# Weihnachtsstern.net
KiCad netlist of a schematic drawn in EAGLE
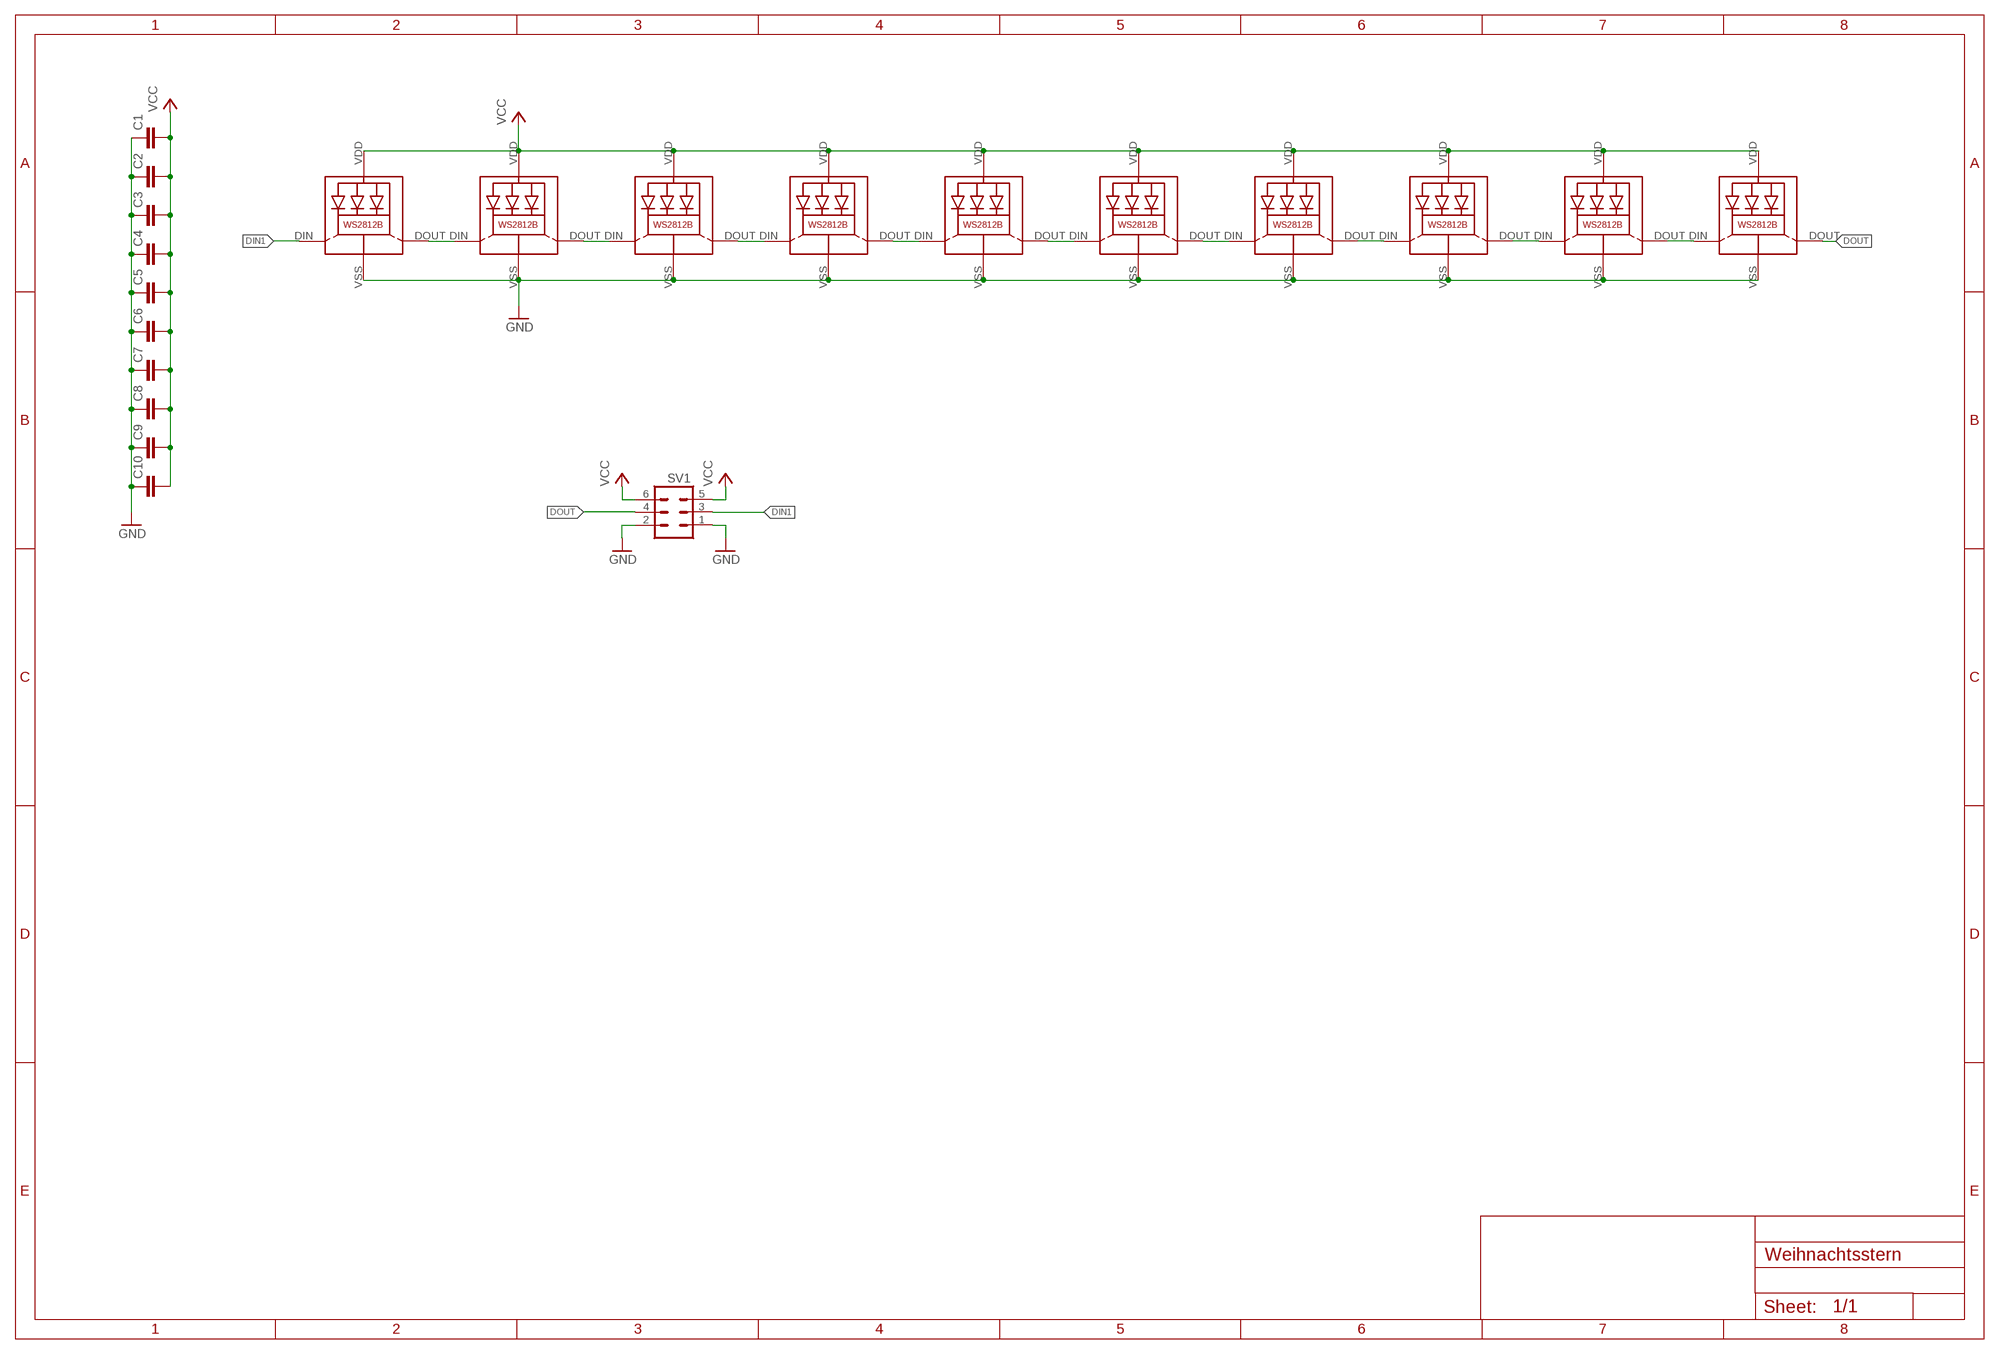
[diagram p0: schematic, sheet 1]

(export (version "E")
  (design (tool "Eeschema 10.0.6"))
  (components
    (comp (ref "C1")
      (value "C-EUC0805")
      (footprint "eagle-import:C0805")
      (libsource (lib "eagle-import") (part "C-EUC0805"))
    )
    (comp (ref "C2")
      (value "C-EUC0805")
      (footprint "eagle-import:C0805")
      (libsource (lib "eagle-import") (part "C-EUC0805"))
    )
    (comp (ref "C3")
      (value "C-EUC0805")
      (footprint "eagle-import:C0805")
      (libsource (lib "eagle-import") (part "C-EUC0805"))
    )
    (comp (ref "C4")
      (value "C-EUC0805")
      (footprint "eagle-import:C0805")
      (libsource (lib "eagle-import") (part "C-EUC0805"))
    )
    (comp (ref "C5")
      (value "C-EUC0805")
      (footprint "eagle-import:C0805")
      (libsource (lib "eagle-import") (part "C-EUC0805"))
    )
    (comp (ref "C6")
      (value "C-EUC0805")
      (footprint "eagle-import:C0805")
      (libsource (lib "eagle-import") (part "C-EUC0805"))
    )
    (comp (ref "C7")
      (value "C-EUC0805")
      (footprint "eagle-import:C0805")
      (libsource (lib "eagle-import") (part "C-EUC0805"))
    )
    (comp (ref "C8")
      (value "C-EUC0805")
      (footprint "eagle-import:C0805")
      (libsource (lib "eagle-import") (part "C-EUC0805"))
    )
    (comp (ref "C9")
      (value "C-EUC0805")
      (footprint "eagle-import:C0805")
      (libsource (lib "eagle-import") (part "C-EUC0805"))
    )
    (comp (ref "C10")
      (value "C-EUC0805")
      (footprint "eagle-import:C0805")
      (libsource (lib "eagle-import") (part "C-EUC0805"))
    )
    (comp (ref "LED1")
      (value "WS2812B")
      (footprint "eagle-import:WS2812B")
      (libsource (lib "eagle-import") (part "WS2812B"))
    )
    (comp (ref "LED2")
      (value "WS2812B")
      (footprint "eagle-import:WS2812B")
      (libsource (lib "eagle-import") (part "WS2812B"))
    )
    (comp (ref "LED3")
      (value "WS2812B")
      (footprint "eagle-import:WS2812B")
      (libsource (lib "eagle-import") (part "WS2812B"))
    )
    (comp (ref "LED4")
      (value "WS2812B")
      (footprint "eagle-import:WS2812B")
      (libsource (lib "eagle-import") (part "WS2812B"))
    )
    (comp (ref "LED5")
      (value "WS2812B")
      (footprint "eagle-import:WS2812B")
      (libsource (lib "eagle-import") (part "WS2812B"))
    )
    (comp (ref "LED6")
      (value "WS2812B")
      (footprint "eagle-import:WS2812B")
      (libsource (lib "eagle-import") (part "WS2812B"))
    )
    (comp (ref "LED7")
      (value "WS2812B")
      (footprint "eagle-import:WS2812B")
      (libsource (lib "eagle-import") (part "WS2812B"))
    )
    (comp (ref "LED8")
      (value "WS2812B")
      (footprint "eagle-import:WS2812B")
      (libsource (lib "eagle-import") (part "WS2812B"))
    )
    (comp (ref "LED9")
      (value "WS2812B")
      (footprint "eagle-import:WS2812B")
      (libsource (lib "eagle-import") (part "WS2812B"))
    )
    (comp (ref "LED10")
      (value "WS2812B")
      (footprint "eagle-import:WS2812B")
      (libsource (lib "eagle-import") (part "WS2812B"))
    )
    (comp (ref "SV1")
      (value "MA03-2")
      (footprint "eagle-import:MA03-2")
      (libsource (lib "eagle-import") (part "MA03-2"))
    )
  )
  (nets
    (net (code "1") (name "DIN1") (class "Default")
      (node (ref "LED1") (pin "DIN") (pinfunction "DI_DIN") (pintype "input"))
      (node (ref "SV1") (pin "3") (pinfunction "3_3") (pintype "passive"))
    )
    (net (code "2") (name "DOUT") (class "Default")
      (node (ref "LED10") (pin "DOUT") (pinfunction "DO_DOUT") (pintype "output"))
      (node (ref "SV1") (pin "4") (pinfunction "4_4") (pintype "passive"))
    )
    (net (code "3") (name "GND") (class "Default")
      (node (ref "C1") (pin "1") (pinfunction "1_1") (pintype "passive"))
      (node (ref "C10") (pin "1") (pinfunction "1_1") (pintype "passive"))
      (node (ref "C2") (pin "1") (pinfunction "1_1") (pintype "passive"))
      (node (ref "C3") (pin "1") (pinfunction "1_1") (pintype "passive"))
      (node (ref "C4") (pin "1") (pinfunction "1_1") (pintype "passive"))
      (node (ref "C5") (pin "1") (pinfunction "1_1") (pintype "passive"))
      (node (ref "C6") (pin "1") (pinfunction "1_1") (pintype "passive"))
      (node (ref "C7") (pin "1") (pinfunction "1_1") (pintype "passive"))
      (node (ref "C8") (pin "1") (pinfunction "1_1") (pintype "passive"))
      (node (ref "C9") (pin "1") (pinfunction "1_1") (pintype "passive"))
      (node (ref "LED1") (pin "VSS") (pinfunction "GND_VSS") (pintype "power_in"))
      (node (ref "LED10") (pin "VSS") (pinfunction "GND_VSS") (pintype "power_in"))
      (node (ref "LED2") (pin "VSS") (pinfunction "GND_VSS") (pintype "power_in"))
      (node (ref "LED3") (pin "VSS") (pinfunction "GND_VSS") (pintype "power_in"))
      (node (ref "LED4") (pin "VSS") (pinfunction "GND_VSS") (pintype "power_in"))
      (node (ref "LED5") (pin "VSS") (pinfunction "GND_VSS") (pintype "power_in"))
      (node (ref "LED6") (pin "VSS") (pinfunction "GND_VSS") (pintype "power_in"))
      (node (ref "LED7") (pin "VSS") (pinfunction "GND_VSS") (pintype "power_in"))
      (node (ref "LED8") (pin "VSS") (pinfunction "GND_VSS") (pintype "power_in"))
      (node (ref "LED9") (pin "VSS") (pinfunction "GND_VSS") (pintype "power_in"))
      (node (ref "SV1") (pin "1") (pinfunction "1_1") (pintype "passive"))
      (node (ref "SV1") (pin "2") (pinfunction "2_2") (pintype "passive"))
    )
    (net (code "4") (name "Net-(LED1-DO)") (class "Default")
      (node (ref "LED1") (pin "DOUT") (pinfunction "DO_DOUT") (pintype "output"))
      (node (ref "LED2") (pin "DIN") (pinfunction "DI_DIN") (pintype "input"))
    )
    (net (code "5") (name "Net-(LED2-DO)") (class "Default")
      (node (ref "LED2") (pin "DOUT") (pinfunction "DO_DOUT") (pintype "output"))
      (node (ref "LED3") (pin "DIN") (pinfunction "DI_DIN") (pintype "input"))
    )
    (net (code "6") (name "Net-(LED3-DO)") (class "Default")
      (node (ref "LED3") (pin "DOUT") (pinfunction "DO_DOUT") (pintype "output"))
      (node (ref "LED4") (pin "DIN") (pinfunction "DI_DIN") (pintype "input"))
    )
    (net (code "7") (name "Net-(LED4-DO)") (class "Default")
      (node (ref "LED4") (pin "DOUT") (pinfunction "DO_DOUT") (pintype "output"))
      (node (ref "LED5") (pin "DIN") (pinfunction "DI_DIN") (pintype "input"))
    )
    (net (code "8") (name "Net-(LED5-DO)") (class "Default")
      (node (ref "LED5") (pin "DOUT") (pinfunction "DO_DOUT") (pintype "output"))
      (node (ref "LED6") (pin "DIN") (pinfunction "DI_DIN") (pintype "input"))
    )
    (net (code "9") (name "Net-(LED6-DO)") (class "Default")
      (node (ref "LED6") (pin "DOUT") (pinfunction "DO_DOUT") (pintype "output"))
      (node (ref "LED7") (pin "DIN") (pinfunction "DI_DIN") (pintype "input"))
    )
    (net (code "10") (name "Net-(LED7-DO)") (class "Default")
      (node (ref "LED7") (pin "DOUT") (pinfunction "DO_DOUT") (pintype "output"))
      (node (ref "LED8") (pin "DIN") (pinfunction "DI_DIN") (pintype "input"))
    )
    (net (code "11") (name "Net-(LED8-DO)") (class "Default")
      (node (ref "LED8") (pin "DOUT") (pinfunction "DO_DOUT") (pintype "output"))
      (node (ref "LED9") (pin "DIN") (pinfunction "DI_DIN") (pintype "input"))
    )
    (net (code "12") (name "Net-(LED10-DI)") (class "Default")
      (node (ref "LED10") (pin "DIN") (pinfunction "DI_DIN") (pintype "input"))
      (node (ref "LED9") (pin "DOUT") (pinfunction "DO_DOUT") (pintype "output"))
    )
    (net (code "13") (name "VCC") (class "Default")
      (node (ref "C1") (pin "2") (pinfunction "2_2") (pintype "passive"))
      (node (ref "C10") (pin "2") (pinfunction "2_2") (pintype "passive"))
      (node (ref "C2") (pin "2") (pinfunction "2_2") (pintype "passive"))
      (node (ref "C3") (pin "2") (pinfunction "2_2") (pintype "passive"))
      (node (ref "C4") (pin "2") (pinfunction "2_2") (pintype "passive"))
      (node (ref "C5") (pin "2") (pinfunction "2_2") (pintype "passive"))
      (node (ref "C6") (pin "2") (pinfunction "2_2") (pintype "passive"))
      (node (ref "C7") (pin "2") (pinfunction "2_2") (pintype "passive"))
      (node (ref "C8") (pin "2") (pinfunction "2_2") (pintype "passive"))
      (node (ref "C9") (pin "2") (pinfunction "2_2") (pintype "passive"))
      (node (ref "LED1") (pin "VDD") (pinfunction "VDD_VDD") (pintype "power_in"))
      (node (ref "LED10") (pin "VDD") (pinfunction "VDD_VDD") (pintype "power_in"))
      (node (ref "LED2") (pin "VDD") (pinfunction "VDD_VDD") (pintype "power_in"))
      (node (ref "LED3") (pin "VDD") (pinfunction "VDD_VDD") (pintype "power_in"))
      (node (ref "LED4") (pin "VDD") (pinfunction "VDD_VDD") (pintype "power_in"))
      (node (ref "LED5") (pin "VDD") (pinfunction "VDD_VDD") (pintype "power_in"))
      (node (ref "LED6") (pin "VDD") (pinfunction "VDD_VDD") (pintype "power_in"))
      (node (ref "LED7") (pin "VDD") (pinfunction "VDD_VDD") (pintype "power_in"))
      (node (ref "LED8") (pin "VDD") (pinfunction "VDD_VDD") (pintype "power_in"))
      (node (ref "LED9") (pin "VDD") (pinfunction "VDD_VDD") (pintype "power_in"))
      (node (ref "SV1") (pin "5") (pinfunction "5_5") (pintype "passive"))
      (node (ref "SV1") (pin "6") (pinfunction "6_6") (pintype "passive"))
    )
  )
)
